# MAC.net
KiCad netlist of a schematic drawn in Altium Designer
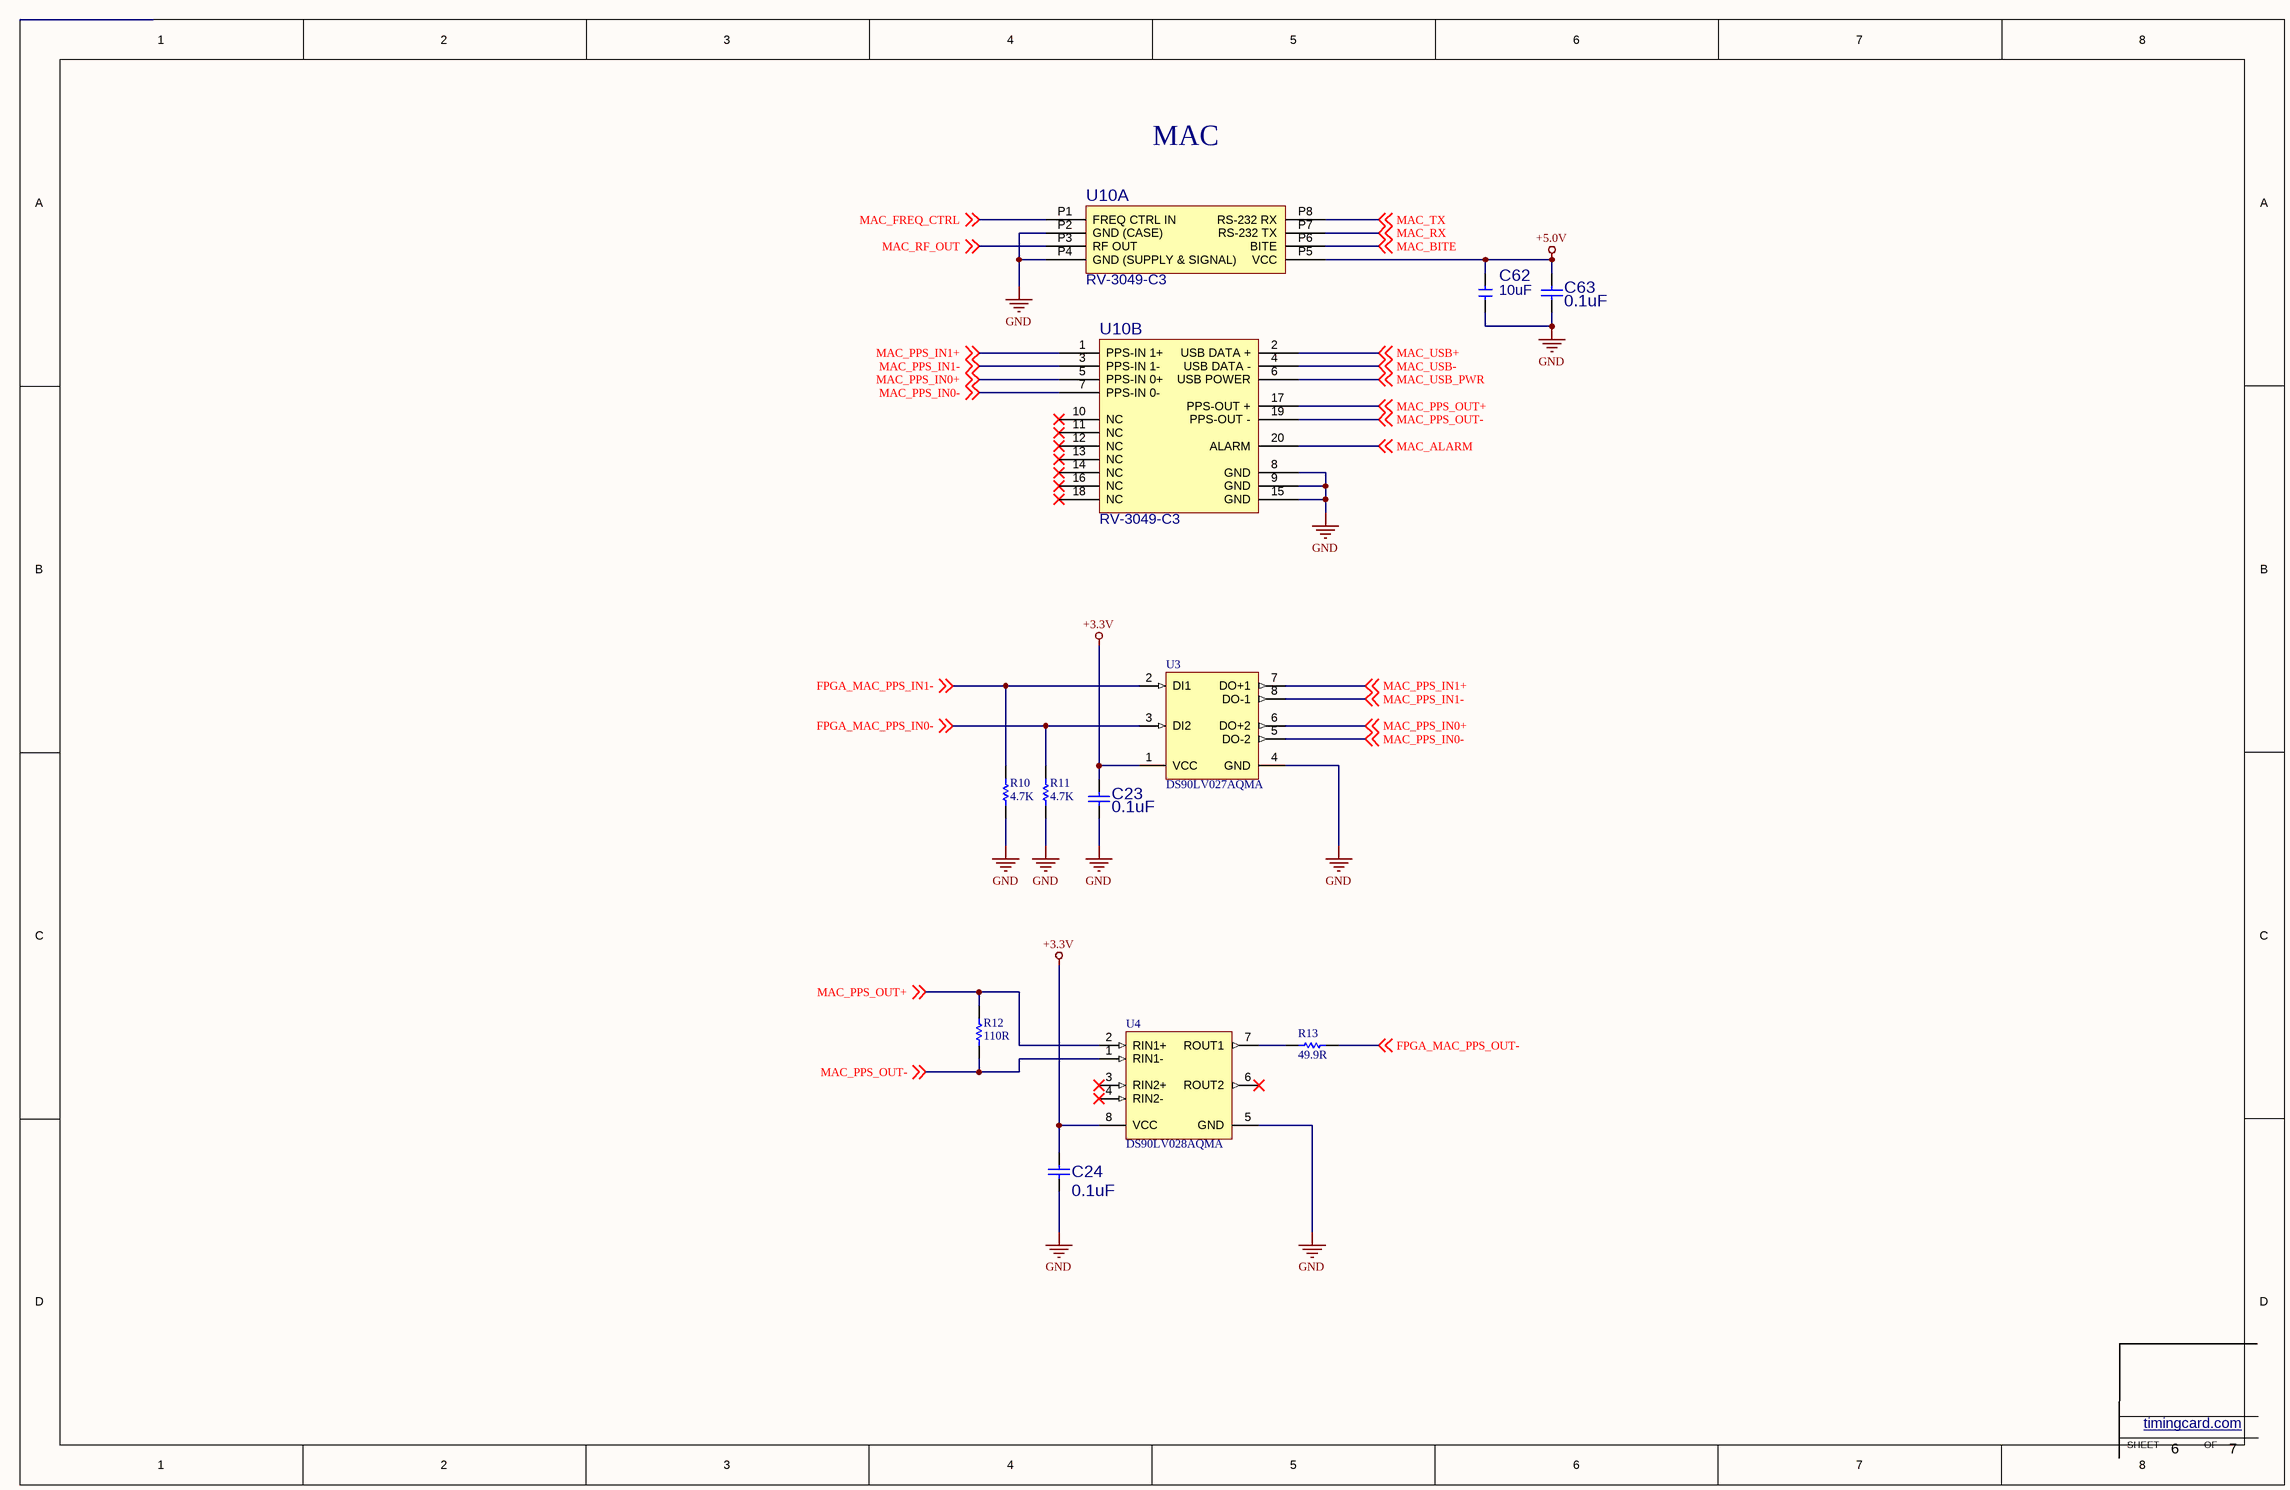
[diagram p0: MAC.SchDoc]

(export (version "E")
  (design (tool "Eeschema 10.0.6"))
  (components
    (comp (ref "C23")
      (value "0.1uF")
      (footprint "CAPC1608X87X45ML20T05")
      (description "C0603X104K5RACAUTO")
      (fields (field (name "MANUFACTURER") "Kemet"))
      (libsource (lib "Altium Content Vault") (part "CAP"))
    )
    (comp (ref "C24")
      (value "0.1uF")
      (footprint "CAPC1608X87X45ML20T05")
      (description "C0603X104K5RACAUTO")
      (fields (field (name "MANUFACTURER") "Kemet"))
      (libsource (lib "Altium Content Vault") (part "CAP"))
    )
    (comp (ref "C62")
      (value "10uF")
      (footprint "CAPC2012X14N")
      (description "CAP, CER, 10.UF, 25V, 10%, X5R, 0805")
      (fields
        (field (name "MFG PART NUM") "TMK212BBJ106KG-T")
        (field (name "VALENTIUM PART NUM") "<VALENTIUM>")
      )
      (libsource (lib "Capacitors") (part "CAP_0805_10UF_25V"))
    )
    (comp (ref "C63")
      (value "0.1uF")
      (footprint "CAPC1608X87X45ML20T05")
      (description "C0603X104K5RACAUTO")
      (fields (field (name "MANUFACTURER") "Kemet"))
      (libsource (lib "Altium Content Vault") (part "CAP"))
    )
    (comp (ref "R10")
      (value "4.7K")
      (footprint "RESC1608X55X25LL10T15")
      (fields (field (name "MANUFACTURER") "Yageo") (field (name "TOLERANCE") "1%"))
      (libsource (lib "Altium Content Vault") (part "RES-2"))
    )
    (comp (ref "R11")
      (value "4.7K")
      (footprint "RESC1608X55X25LL10T15")
      (fields (field (name "MANUFACTURER") "Yageo") (field (name "TOLERANCE") "1%"))
      (libsource (lib "Altium Content Vault") (part "RES-2"))
    )
    (comp (ref "R12")
      (value "110R")
      (footprint "RESC1609X50X30NL10T20")
      (fields (field (name "PART NUMBER") "CRCW0603110RFKEA") (field (name "MANUFACTURER") "Vishay Dale"))
      (libsource (lib "Altium Content Vault") (part "RES"))
    )
    (comp (ref "R13")
      (value "49.9R")
      (footprint "RESC1608X55X25NL10T15")
      (libsource (lib "Altium Content Vault") (part "RES-2"))
    )
    (comp (ref "U3")
      (value "DS90LV027AQMA")
      (footprint "M08A_N")
      (description "Automotive LVDS Dual Differential Driver, 8-pin Narrow SOIC")
      (fields (field (name "MANUFACTURER") "National Semiconductor"))
      (libsource (lib "Altium Content Vault") (part "IN-LNDRV-DS90LV027AHM"))
    )
    (comp (ref "U4")
      (value "DS90LV028AQMA")
      (footprint "M08A_L")
      (description "Automotive LVDS Dual Differential Line Receiver, 8-pin Narrow SOIC")
      (fields (field (name "MANUFACTURER") "National Semiconductor"))
      (libsource (lib "Altium Content Vault") (part "IN-LNRX-DS90LV028AHM"))
    )
    (comp (ref "U10")
      (value "RV-3049-C3")
      (footprint "SA53")
      (description "MOD, MAC, MAC-SA5X, ATOMIC CLOCK")
      (fields (field (name "MFG PART NUM") "MAC-SA5X") (field (name "VELENTIUM PART NUM") "<V PART NUM>"))
      (libsource (lib "Modules") (part "MAC-SA5X"))
    )
  )
  (nets
    (net (code "1") (name "+3.3V") (class "Default")
      (node (ref "C23") (pin "2") (pinfunction "2_2") (pintype "passive"))
      (node (ref "C24") (pin "1") (pinfunction "1_1") (pintype "passive"))
      (node (ref "U3") (pin "1") (pinfunction "VCC_1") (pintype "power_in"))
      (node (ref "U4") (pin "8") (pinfunction "VCC_8") (pintype "power_in"))
    )
    (net (code "2") (name "+5.0V") (class "Default")
      (node (ref "C62") (pin "1") (pinfunction "1_1") (pintype "passive"))
      (node (ref "C63") (pin "2") (pinfunction "2_2") (pintype "passive"))
      (node (ref "U10") (pin "P5") (pinfunction "VCC_P5") (pintype "passive"))
    )
    (net (code "3") (name "FPGA_MAC_PPS_IN0-") (class "Default")
      (node (ref "R11") (pin "2") (pinfunction "2_2") (pintype "passive"))
      (node (ref "U3") (pin "3") (pinfunction "DI2_3") (pintype "input"))
    )
    (net (code "4") (name "FPGA_MAC_PPS_IN1-") (class "Default")
      (node (ref "R10") (pin "2") (pinfunction "2_2") (pintype "passive"))
      (node (ref "U3") (pin "2") (pinfunction "DI1_2") (pintype "input"))
    )
    (net (code "5") (name "FPGA_MAC_PPS_OUT-") (class "Default")
      (node (ref "R13") (pin "2") (pinfunction "2_2") (pintype "passive"))
    )
    (net (code "6") (name "GND") (class "Default")
      (node (ref "C23") (pin "1") (pinfunction "1_1") (pintype "passive"))
      (node (ref "C24") (pin "2") (pinfunction "2_2") (pintype "passive"))
      (node (ref "C62") (pin "2") (pinfunction "2_2") (pintype "passive"))
      (node (ref "C63") (pin "1") (pinfunction "1_1") (pintype "passive"))
      (node (ref "R10") (pin "1") (pinfunction "1_1") (pintype "passive"))
      (node (ref "R11") (pin "1") (pinfunction "1_1") (pintype "passive"))
      (node (ref "U10") (pin "15") (pinfunction "GND_15") (pintype "passive"))
      (node (ref "U10") (pin "8") (pinfunction "GND_8") (pintype "passive"))
      (node (ref "U10") (pin "9") (pinfunction "GND_9") (pintype "passive"))
      (node (ref "U10") (pin "P2") (pinfunction "GND_(CASE)_P2") (pintype "passive"))
      (node (ref "U10") (pin "P4") (pinfunction "GND_(SUPPLY_&_SIGNAL)_P4") (pintype "passive"))
      (node (ref "U3") (pin "4") (pinfunction "GND_4") (pintype "power_in"))
      (node (ref "U4") (pin "5") (pinfunction "GND_5") (pintype "power_in"))
    )
    (net (code "7") (name "MAC_ALARM") (class "Default")
      (node (ref "U10") (pin "20") (pinfunction "ALARM_20") (pintype "passive"))
    )
    (net (code "8") (name "MAC_BITE") (class "Default")
      (node (ref "U10") (pin "P6") (pinfunction "BITE_P6") (pintype "passive"))
    )
    (net (code "9") (name "MAC_FREQ_CTRL") (class "Default")
      (node (ref "U10") (pin "P1") (pinfunction "FREQ_CTRL_IN_P1") (pintype "passive"))
    )
    (net (code "10") (name "MAC_PPS_IN0+") (class "Default")
      (node (ref "U10") (pin "5") (pinfunction "PPS-IN_0+_5") (pintype "passive"))
      (node (ref "U3") (pin "6") (pinfunction "DO+2_6") (pintype "output"))
    )
    (net (code "11") (name "MAC_PPS_IN0-") (class "Default")
      (node (ref "U10") (pin "7") (pinfunction "PPS-IN_0-_7") (pintype "passive"))
      (node (ref "U3") (pin "5") (pinfunction "DO-2_5") (pintype "output"))
    )
    (net (code "12") (name "MAC_PPS_IN1+") (class "Default")
      (node (ref "U10") (pin "1") (pinfunction "PPS-IN_1+_1") (pintype "passive"))
      (node (ref "U3") (pin "7") (pinfunction "DO+1_7") (pintype "output"))
    )
    (net (code "13") (name "MAC_PPS_IN1-") (class "Default")
      (node (ref "U10") (pin "3") (pinfunction "PPS-IN_1-_3") (pintype "passive"))
      (node (ref "U3") (pin "8") (pinfunction "DO-1_8") (pintype "output"))
    )
    (net (code "14") (name "MAC_PPS_OUT+") (class "Default")
      (node (ref "R12") (pin "2") (pinfunction "2_2") (pintype "passive"))
      (node (ref "U10") (pin "17") (pinfunction "PPS-OUT_+_17") (pintype "passive"))
      (node (ref "U4") (pin "2") (pinfunction "RIN1+_2") (pintype "input"))
    )
    (net (code "15") (name "MAC_PPS_OUT-") (class "Default")
      (node (ref "R12") (pin "1") (pinfunction "1_1") (pintype "passive"))
      (node (ref "U10") (pin "19") (pinfunction "PPS-OUT_-_19") (pintype "passive"))
      (node (ref "U4") (pin "1") (pinfunction "RIN1-_1") (pintype "input"))
    )
    (net (code "16") (name "MAC_RF_OUT") (class "Default")
      (node (ref "U10") (pin "P3") (pinfunction "RF_OUT_P3") (pintype "passive"))
    )
    (net (code "17") (name "MAC_RX") (class "Default")
      (node (ref "U10") (pin "P7") (pinfunction "RS-232_TX_P7") (pintype "passive"))
    )
    (net (code "18") (name "MAC_TX") (class "Default")
      (node (ref "U10") (pin "P8") (pinfunction "RS-232_RX_P8") (pintype "passive"))
    )
    (net (code "19") (name "MAC_USB+") (class "Default")
      (node (ref "U10") (pin "2") (pinfunction "USB_DATA_+_2") (pintype "passive"))
    )
    (net (code "20") (name "MAC_USB-") (class "Default")
      (node (ref "U10") (pin "4") (pinfunction "USB_DATA_-_4") (pintype "passive"))
    )
    (net (code "21") (name "MAC_USB_PWR") (class "Default")
      (node (ref "U10") (pin "6") (pinfunction "USB_POWER_6") (pintype "passive"))
    )
    (net (code "22") (name "Net-(U4-ROUT1)") (class "Default")
      (node (ref "R13") (pin "1") (pinfunction "1_1") (pintype "passive"))
      (node (ref "U4") (pin "7") (pinfunction "ROUT1_7") (pintype "output"))
    )
    (net (code "23") (name "unconnected-(U4-RIN2+-Pad3)") (class "Default")
      (node (ref "U4") (pin "3") (pinfunction "RIN2+_3") (pintype "input+no_connect"))
    )
    (net (code "24") (name "unconnected-(U4-RIN2--Pad4)") (class "Default")
      (node (ref "U4") (pin "4") (pinfunction "RIN2-_4") (pintype "input+no_connect"))
    )
    (net (code "25") (name "unconnected-(U4-ROUT2-Pad6)") (class "Default")
      (node (ref "U4") (pin "6") (pinfunction "ROUT2_6") (pintype "output+no_connect"))
    )
    (net (code "26") (name "unconnected-(U10B-NC-Pad10)") (class "Default")
      (node (ref "U10") (pin "10") (pinfunction "NC_10") (pintype "passive+no_connect"))
    )
    (net (code "27") (name "unconnected-(U10B-NC-Pad11)") (class "Default")
      (node (ref "U10") (pin "11") (pinfunction "NC_11") (pintype "passive+no_connect"))
    )
    (net (code "28") (name "unconnected-(U10B-NC-Pad12)") (class "Default")
      (node (ref "U10") (pin "12") (pinfunction "NC_12") (pintype "passive+no_connect"))
    )
    (net (code "29") (name "unconnected-(U10B-NC-Pad13)") (class "Default")
      (node (ref "U10") (pin "13") (pinfunction "NC_13") (pintype "passive+no_connect"))
    )
    (net (code "30") (name "unconnected-(U10B-NC-Pad14)") (class "Default")
      (node (ref "U10") (pin "14") (pinfunction "NC_14") (pintype "passive+no_connect"))
    )
    (net (code "31") (name "unconnected-(U10B-NC-Pad16)") (class "Default")
      (node (ref "U10") (pin "16") (pinfunction "NC_16") (pintype "passive+no_connect"))
    )
    (net (code "32") (name "unconnected-(U10B-NC-Pad18)") (class "Default")
      (node (ref "U10") (pin "18") (pinfunction "NC_18") (pintype "passive+no_connect"))
    )
  )
)
